# TP_IHM_7SEG.net
KiCad netlist of a schematic drawn in Altium Designer
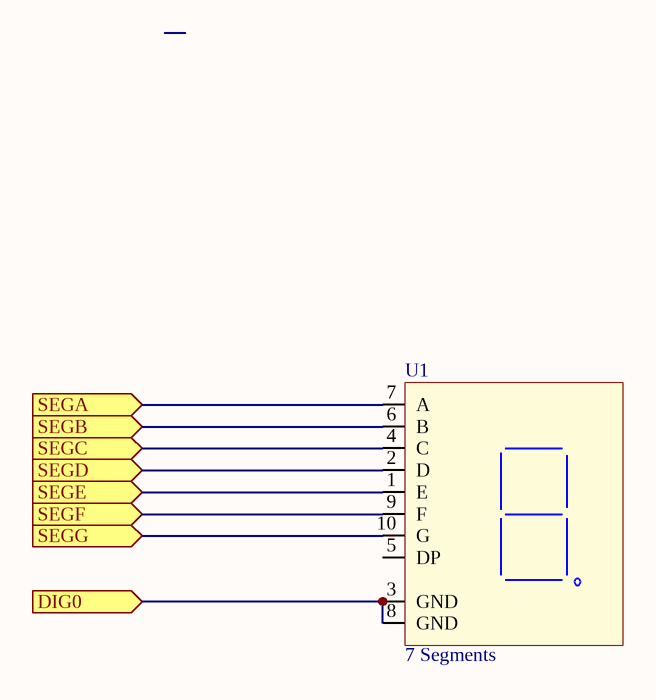
[diagram p0: TP_IHM_7SEG.SchDoc]

(export (version "E")
  (design (tool "Eeschema 10.0.6"))
  (components
    (comp (ref "U1")
      (value "7 Segments")
      (footprint "SA10-21GWA")
      (description "KingBright Led 7 Segments")
      (libsource (lib "TpGiven") (part "SC10-21SRWA"))
    )
  )
  (nets
    (net (code "1") (name "/DIG0") (class "Default")
      (node (ref "U1") (pin "3") (pinfunction "GND_3") (pintype "passive"))
      (node (ref "U1") (pin "8") (pinfunction "GND_8") (pintype "passive"))
    )
    (net (code "2") (name "/SEGA") (class "Default")
      (node (ref "U1") (pin "7") (pinfunction "A_7") (pintype "passive"))
    )
    (net (code "3") (name "/SEGB") (class "Default")
      (node (ref "U1") (pin "6") (pinfunction "B_6") (pintype "passive"))
    )
    (net (code "4") (name "/SEGC") (class "Default")
      (node (ref "U1") (pin "4") (pinfunction "C_4") (pintype "passive"))
    )
    (net (code "5") (name "/SEGD") (class "Default")
      (node (ref "U1") (pin "2") (pinfunction "D_2") (pintype "passive"))
    )
    (net (code "6") (name "/SEGE") (class "Default")
      (node (ref "U1") (pin "1") (pinfunction "E_1") (pintype "passive"))
    )
    (net (code "7") (name "/SEGF") (class "Default")
      (node (ref "U1") (pin "9") (pinfunction "F_9") (pintype "passive"))
    )
    (net (code "8") (name "/SEGG") (class "Default")
      (node (ref "U1") (pin "10") (pinfunction "G_10") (pintype "passive"))
    )
    (net (code "9") (name "unconnected-(U1-DP-Pad5)") (class "Default")
      (node (ref "U1") (pin "5") (pinfunction "DP_5") (pintype "passive"))
    )
  )
)
